# LIC_rack_ZM-01.net
KiCad netlist of a schematic drawn in EAGLE
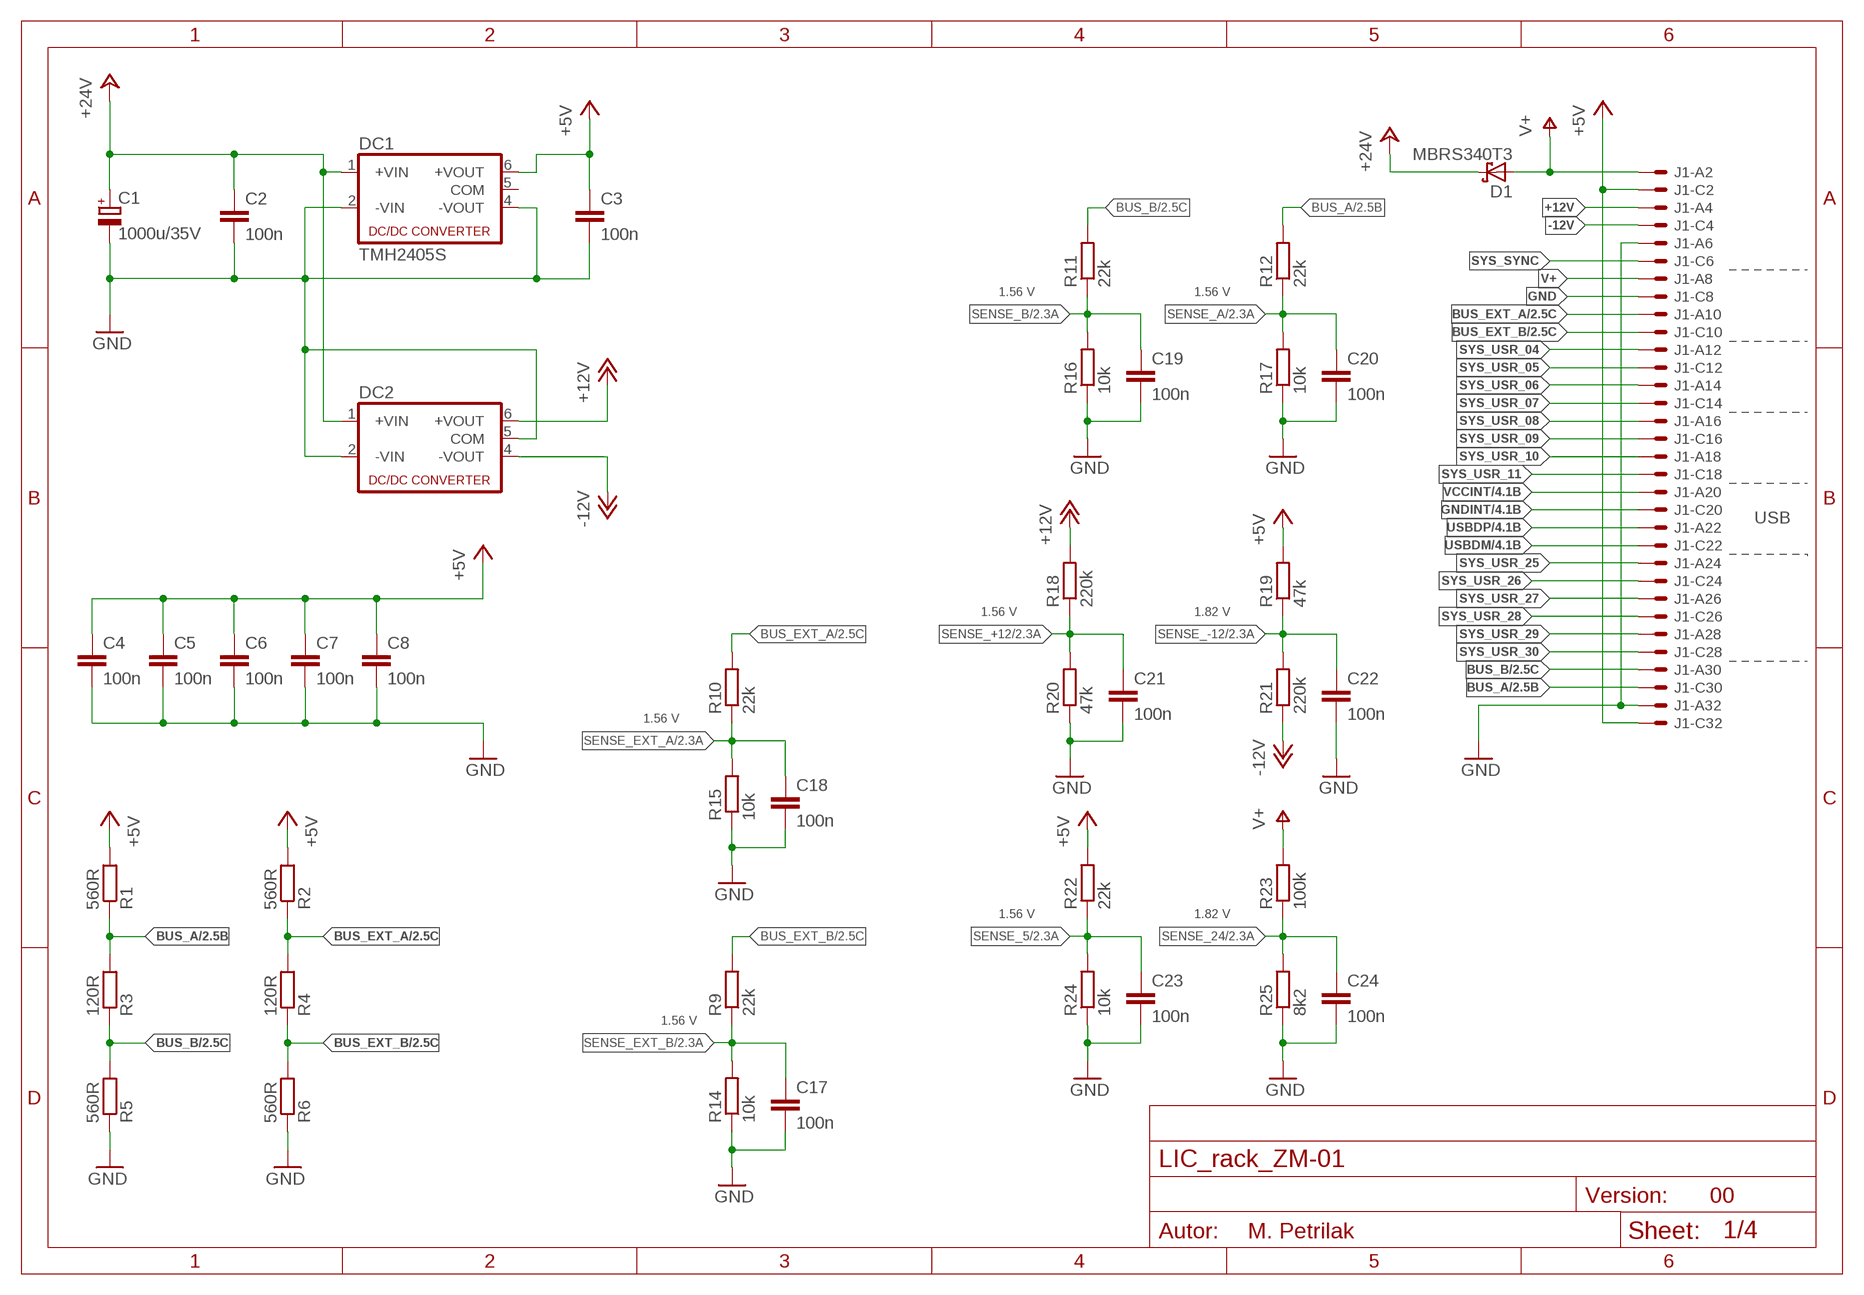
[diagram p0: schematic, sheet 1]
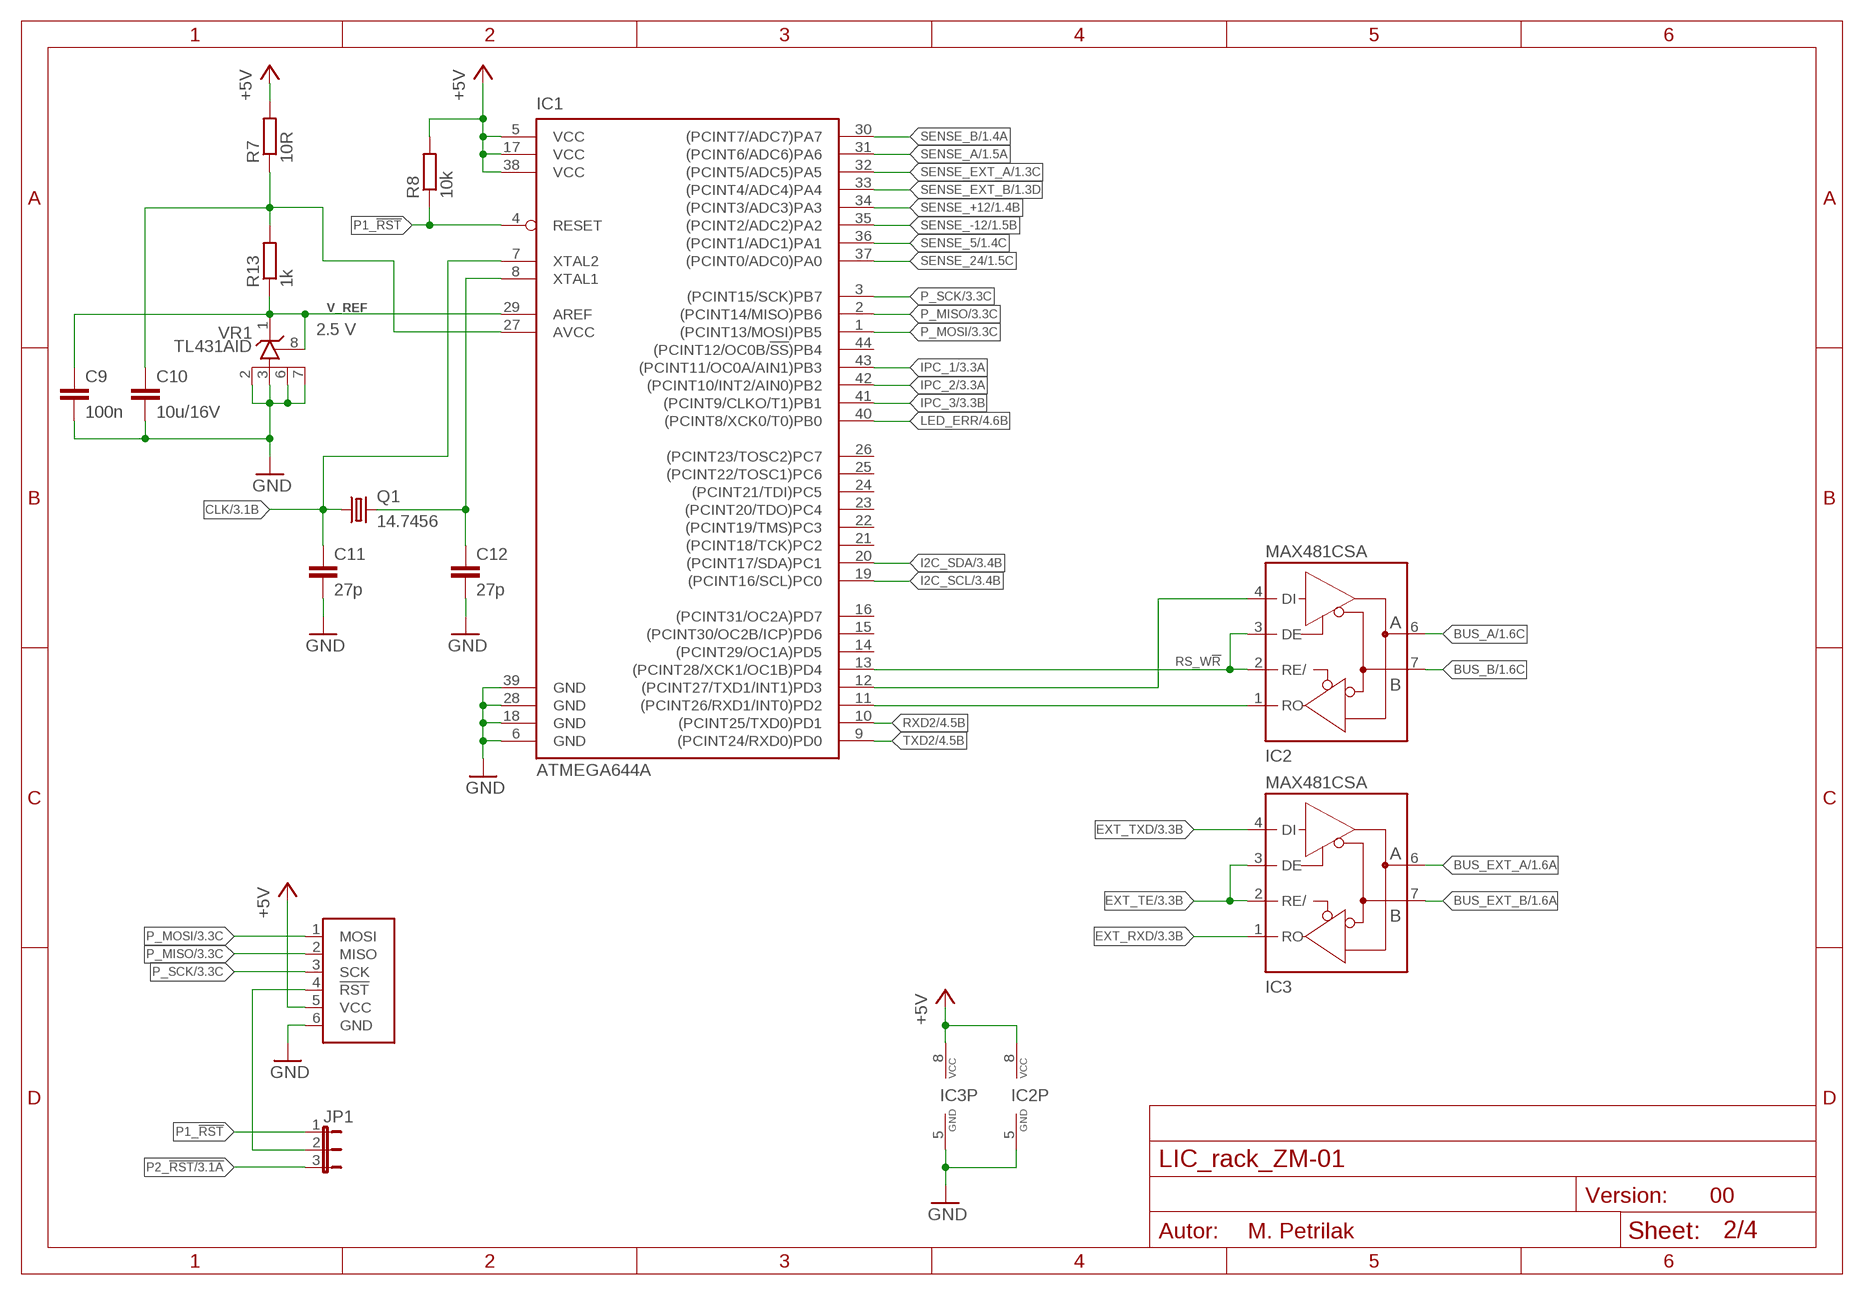
[diagram p1: schematic, sheet 2]
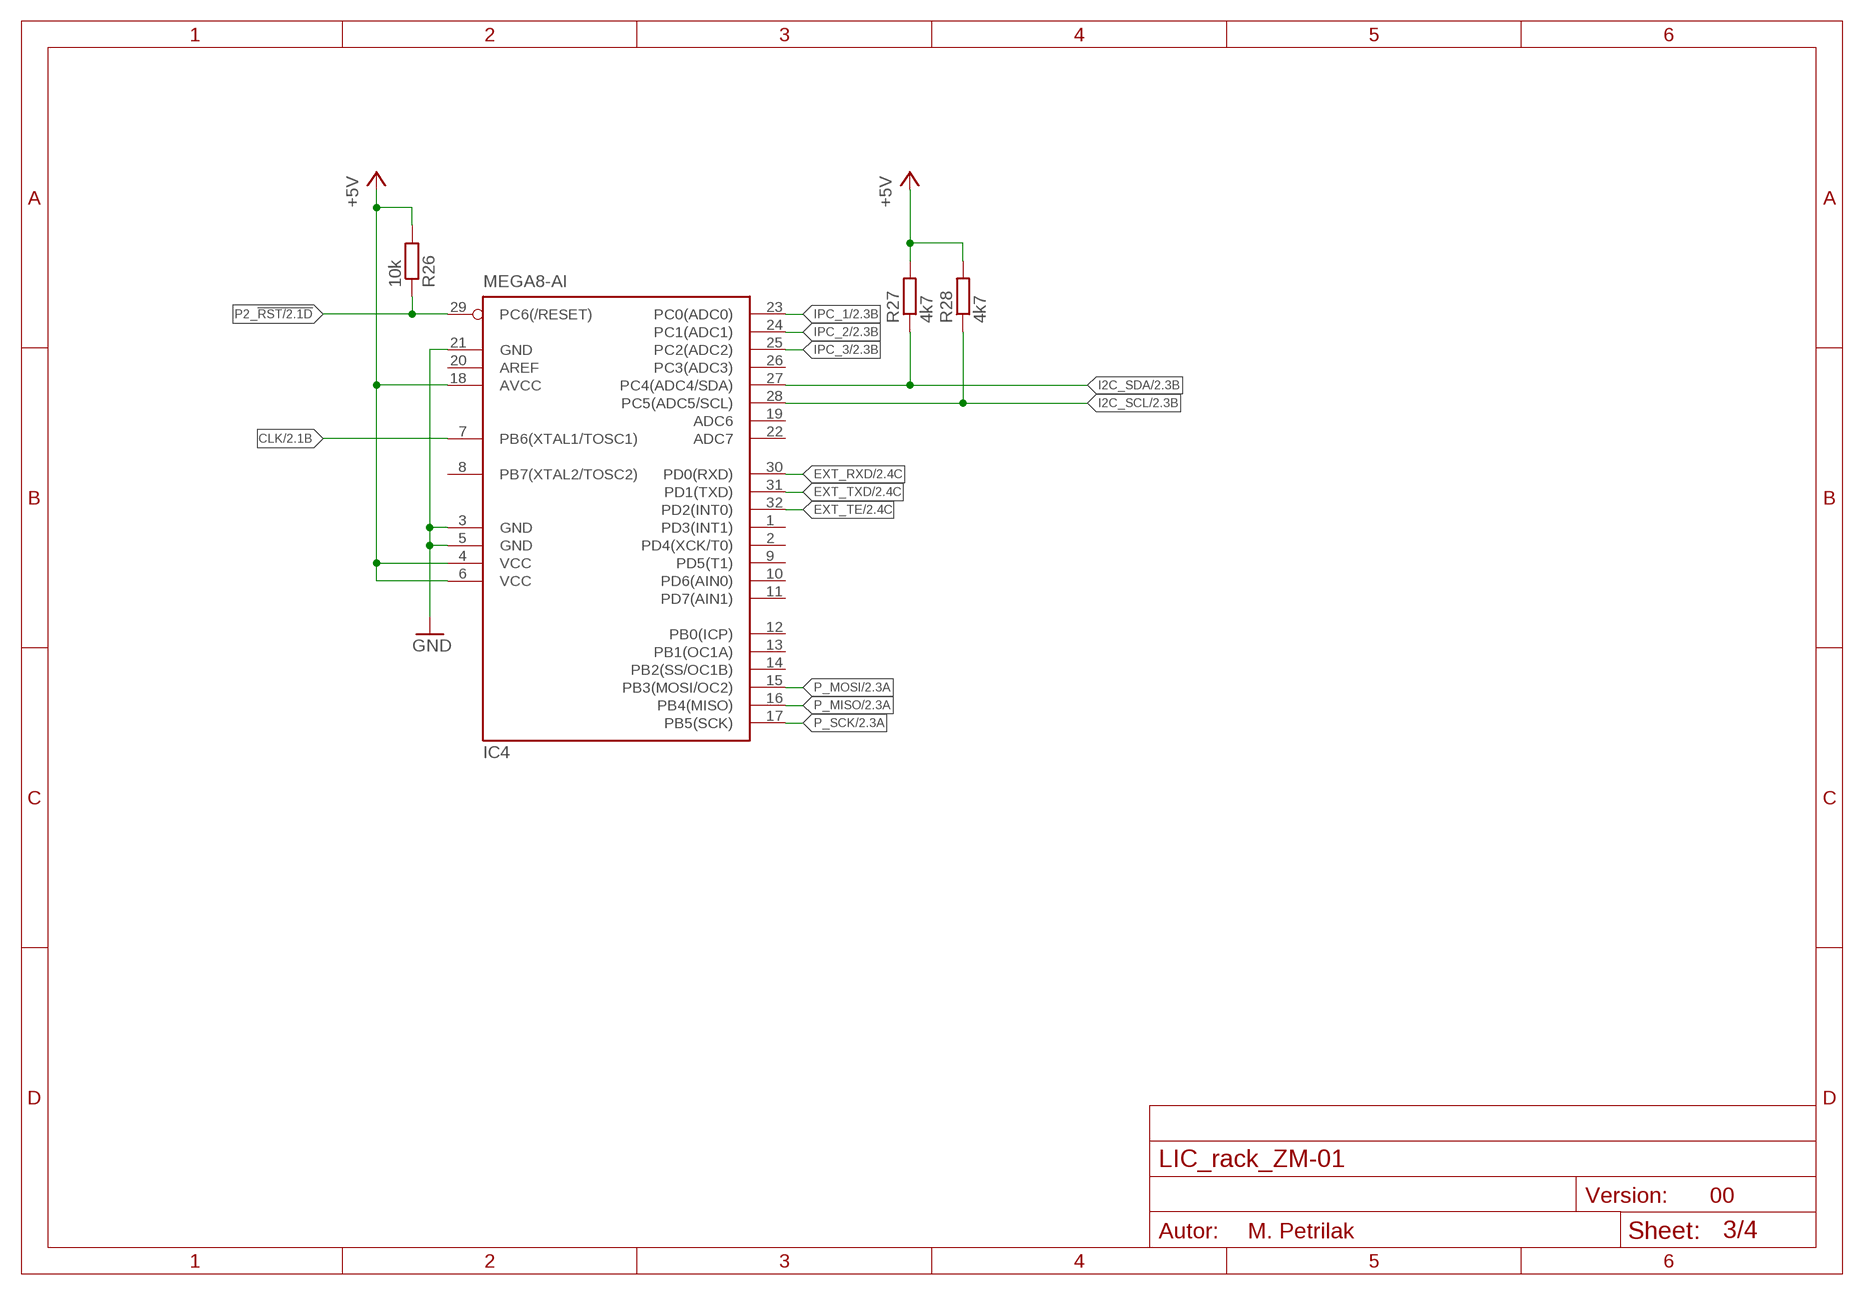
[diagram p2: schematic, sheet 3]
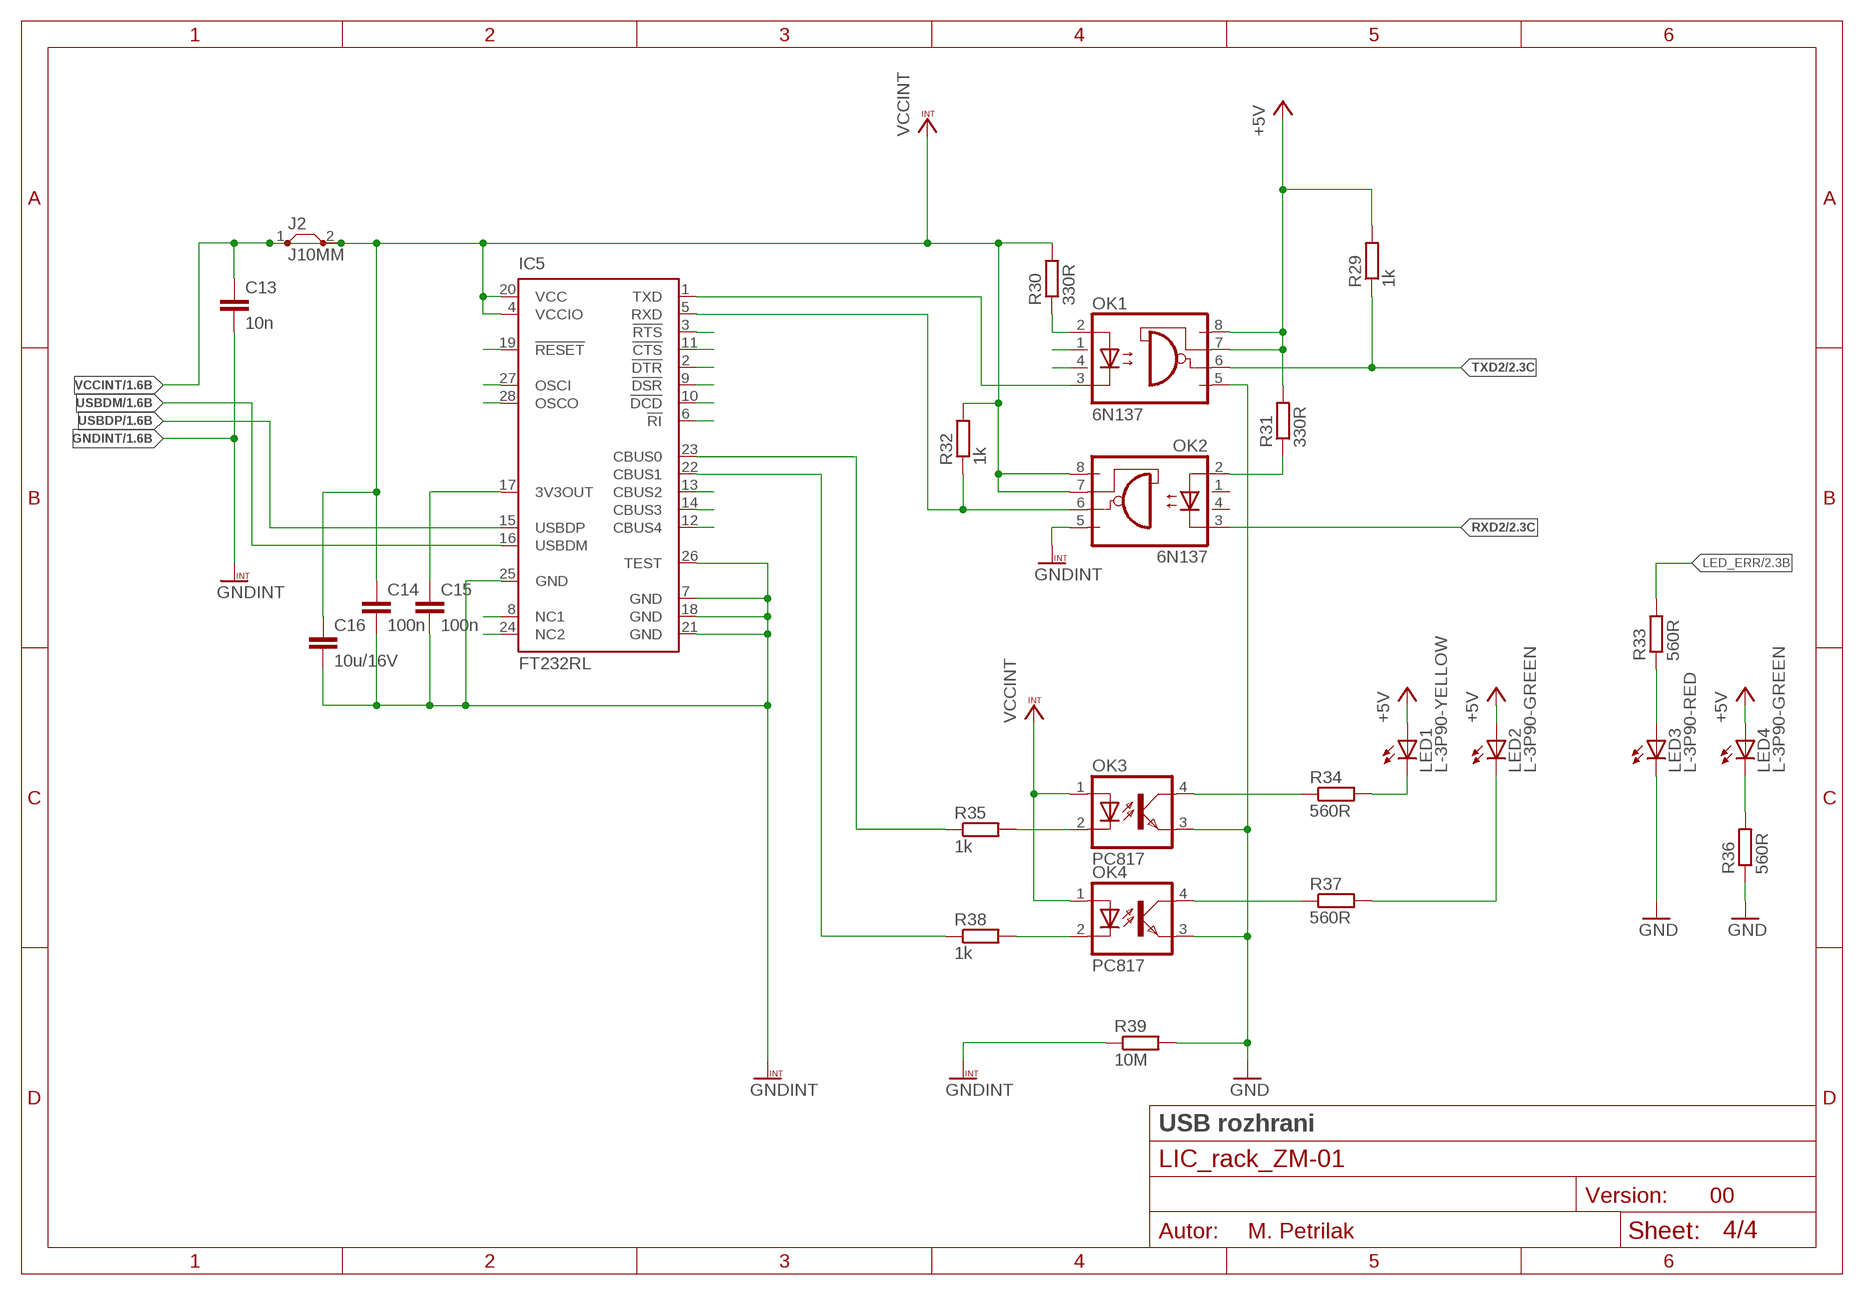
[diagram p3: schematic, sheet 4]

(export (version "E")
  (design (tool "Eeschema 10.0.6"))
  (components
    (comp (ref "C1")
      (value "1000u/35V")
      (footprint "eagle-import:E5-13X26-LR")
      (libsource (lib "eagle-import") (part "CPOL-EUE5-13X26-LR"))
    )
    (comp (ref "C2")
      (value "100n")
      (footprint "eagle-import:C1206")
      (libsource (lib "eagle-import") (part "C-EUC1206"))
    )
    (comp (ref "C3")
      (value "100n")
      (footprint "eagle-import:C1206")
      (libsource (lib "eagle-import") (part "C-EUC1206"))
    )
    (comp (ref "C4")
      (value "100n")
      (footprint "eagle-import:C1206")
      (libsource (lib "eagle-import") (part "C-EUC1206"))
    )
    (comp (ref "C5")
      (value "100n")
      (footprint "eagle-import:C1206")
      (libsource (lib "eagle-import") (part "C-EUC1206"))
    )
    (comp (ref "C6")
      (value "100n")
      (footprint "eagle-import:C1206")
      (libsource (lib "eagle-import") (part "C-EUC1206"))
    )
    (comp (ref "C7")
      (value "100n")
      (footprint "eagle-import:C1206")
      (libsource (lib "eagle-import") (part "C-EUC1206"))
    )
    (comp (ref "C8")
      (value "100n")
      (footprint "eagle-import:C1206")
      (libsource (lib "eagle-import") (part "C-EUC1206"))
    )
    (comp (ref "C17")
      (value "100n")
      (footprint "eagle-import:C1206")
      (libsource (lib "eagle-import") (part "C-EUC1206"))
    )
    (comp (ref "C18")
      (value "100n")
      (footprint "eagle-import:C1206")
      (libsource (lib "eagle-import") (part "C-EUC1206"))
    )
    (comp (ref "C19")
      (value "100n")
      (footprint "eagle-import:C1206")
      (libsource (lib "eagle-import") (part "C-EUC1206"))
    )
    (comp (ref "C20")
      (value "100n")
      (footprint "eagle-import:C1206")
      (libsource (lib "eagle-import") (part "C-EUC1206"))
    )
    (comp (ref "C21")
      (value "100n")
      (footprint "eagle-import:C1206")
      (libsource (lib "eagle-import") (part "C-EUC1206"))
    )
    (comp (ref "C22")
      (value "100n")
      (footprint "eagle-import:C1206")
      (libsource (lib "eagle-import") (part "C-EUC1206"))
    )
    (comp (ref "C23")
      (value "100n")
      (footprint "eagle-import:C1206")
      (libsource (lib "eagle-import") (part "C-EUC1206"))
    )
    (comp (ref "C24")
      (value "100n")
      (footprint "eagle-import:C1206")
      (libsource (lib "eagle-import") (part "C-EUC1206"))
    )
    (comp (ref "D1")
      (value "MBRS340T3")
      (footprint "eagle-import:SMC")
      (libsource (lib "eagle-import") (part "MBRS340T3"))
    )
    (comp (ref "DC1")
      (value "TMH2405S")
      (footprint "eagle-import:NMA")
      (libsource (lib "eagle-import") (part "NMA"))
    )
    (comp (ref "DC2")
      (value "NMA")
      (footprint "eagle-import:NMA")
      (libsource (lib "eagle-import") (part "NMA"))
    )
    (comp (ref "J1")
      (value "VG32SP")
      (footprint "eagle-import:VG32P")
      (libsource (lib "eagle-import") (part "VG32SP"))
    )
    (comp (ref "R1")
      (value "560R")
      (footprint "eagle-import:R1206")
      (libsource (lib "eagle-import") (part "R-EU_R1206"))
    )
    (comp (ref "R2")
      (value "560R")
      (footprint "eagle-import:R1206")
      (libsource (lib "eagle-import") (part "R-EU_R1206"))
    )
    (comp (ref "R3")
      (value "120R")
      (footprint "eagle-import:R1206")
      (libsource (lib "eagle-import") (part "R-EU_R1206"))
    )
    (comp (ref "R4")
      (value "120R")
      (footprint "eagle-import:R1206")
      (libsource (lib "eagle-import") (part "R-EU_R1206"))
    )
    (comp (ref "R5")
      (value "560R")
      (footprint "eagle-import:R1206")
      (libsource (lib "eagle-import") (part "R-EU_R1206"))
    )
    (comp (ref "R6")
      (value "560R")
      (footprint "eagle-import:R1206")
      (libsource (lib "eagle-import") (part "R-EU_R1206"))
    )
    (comp (ref "R9")
      (value "22k")
      (footprint "eagle-import:R1206")
      (libsource (lib "eagle-import") (part "R-EU_R1206"))
    )
    (comp (ref "R10")
      (value "22k")
      (footprint "eagle-import:R1206")
      (libsource (lib "eagle-import") (part "R-EU_R1206"))
    )
    (comp (ref "R11")
      (value "22k")
      (footprint "eagle-import:R1206")
      (libsource (lib "eagle-import") (part "R-EU_R1206"))
    )
    (comp (ref "R12")
      (value "22k")
      (footprint "eagle-import:R1206")
      (libsource (lib "eagle-import") (part "R-EU_R1206"))
    )
    (comp (ref "R14")
      (value "10k")
      (footprint "eagle-import:R1206")
      (libsource (lib "eagle-import") (part "R-EU_R1206"))
    )
    (comp (ref "R15")
      (value "10k")
      (footprint "eagle-import:R1206")
      (libsource (lib "eagle-import") (part "R-EU_R1206"))
    )
    (comp (ref "R16")
      (value "10k")
      (footprint "eagle-import:R1206")
      (libsource (lib "eagle-import") (part "R-EU_R1206"))
    )
    (comp (ref "R17")
      (value "10k")
      (footprint "eagle-import:R1206")
      (libsource (lib "eagle-import") (part "R-EU_R1206"))
    )
    (comp (ref "R18")
      (value "220k")
      (footprint "eagle-import:R1206")
      (libsource (lib "eagle-import") (part "R-EU_R1206"))
    )
    (comp (ref "R19")
      (value "47k")
      (footprint "eagle-import:R1206")
      (libsource (lib "eagle-import") (part "R-EU_R1206"))
    )
    (comp (ref "R20")
      (value "47k")
      (footprint "eagle-import:R1206")
      (libsource (lib "eagle-import") (part "R-EU_R1206"))
    )
    (comp (ref "R21")
      (value "220k")
      (footprint "eagle-import:R1206")
      (libsource (lib "eagle-import") (part "R-EU_R1206"))
    )
    (comp (ref "R22")
      (value "22k")
      (footprint "eagle-import:R1206")
      (libsource (lib "eagle-import") (part "R-EU_R1206"))
    )
    (comp (ref "R23")
      (value "100k")
      (footprint "eagle-import:R1206")
      (libsource (lib "eagle-import") (part "R-EU_R1206"))
    )
    (comp (ref "R24")
      (value "10k")
      (footprint "eagle-import:R1206")
      (libsource (lib "eagle-import") (part "R-EU_R1206"))
    )
    (comp (ref "R25")
      (value "8k2")
      (footprint "eagle-import:R1206")
      (libsource (lib "eagle-import") (part "R-EU_R1206"))
    )
    (comp (ref "C9")
      (value "100n")
      (footprint "eagle-import:C1206")
      (libsource (lib "eagle-import") (part "C-EUC1206"))
    )
    (comp (ref "C10")
      (value "10u/16V")
      (footprint "eagle-import:C1206")
      (libsource (lib "eagle-import") (part "C-EUC1206"))
    )
    (comp (ref "C11")
      (value "27p")
      (footprint "eagle-import:C0805")
      (libsource (lib "eagle-import") (part "C-EUC0805"))
    )
    (comp (ref "C12")
      (value "27p")
      (footprint "eagle-import:C0805")
      (libsource (lib "eagle-import") (part "C-EUC0805"))
    )
    (comp (ref "IC1")
      (value "ATMEGA644A")
      (footprint "eagle-import:TQFP44")
      (libsource (lib "eagle-import") (part "ATMEGA644A"))
    )
    (comp (ref "IC2")
      (value "MAX481CSA")
      (footprint "eagle-import:SO08")
      (libsource (lib "eagle-import") (part "MAX481CSA"))
    )
    (comp (ref "IC3")
      (value "MAX481CSA")
      (footprint "eagle-import:SO08")
      (libsource (lib "eagle-import") (part "MAX481CSA"))
    )
    (comp (ref "JP1")
      (value "JP2E")
      (footprint "eagle-import:JP2")
      (libsource (lib "eagle-import") (part "JP2E"))
    )
    (comp (ref "Q1")
      (value "14.7456")
      (footprint "eagle-import:HC49U70")
      (libsource (lib "eagle-import") (part "XTAL"))
    )
    (comp (ref "R7")
      (value "10R")
      (footprint "eagle-import:R1206")
      (libsource (lib "eagle-import") (part "R-EU_R1206"))
    )
    (comp (ref "R8")
      (value "10k")
      (footprint "eagle-import:R1206")
      (libsource (lib "eagle-import") (part "R-EU_R1206"))
    )
    (comp (ref "R13")
      (value "1k")
      (footprint "eagle-import:R1206")
      (libsource (lib "eagle-import") (part "R-EU_R1206"))
    )
    (comp (ref "U1")
      (value "ATPROG-V")
      (footprint "eagle-import:6410-06")
      (libsource (lib "eagle-import") (part "ATPROG-V"))
    )
    (comp (ref "VR1")
      (value "TL431AID")
      (footprint "eagle-import:SO-08")
      (libsource (lib "eagle-import") (part "TL431-SMD"))
    )
    (comp (ref "IC4")
      (value "MEGA8-AI")
      (footprint "eagle-import:TQFP32-08")
      (libsource (lib "eagle-import") (part "MEGA8-AI"))
    )
    (comp (ref "R26")
      (value "10k")
      (footprint "eagle-import:R1206")
      (libsource (lib "eagle-import") (part "R-EU_R1206"))
    )
    (comp (ref "R27")
      (value "4k7")
      (footprint "eagle-import:R1206")
      (libsource (lib "eagle-import") (part "R-EU_R1206"))
    )
    (comp (ref "R28")
      (value "4k7")
      (footprint "eagle-import:R1206")
      (libsource (lib "eagle-import") (part "R-EU_R1206"))
    )
    (comp (ref "C13")
      (value "10n")
      (footprint "eagle-import:C0805")
      (libsource (lib "eagle-import") (part "C-EUC0805"))
    )
    (comp (ref "C14")
      (value "100n")
      (footprint "eagle-import:C1206")
      (libsource (lib "eagle-import") (part "C-EUC1206"))
    )
    (comp (ref "C15")
      (value "100n")
      (footprint "eagle-import:C1206")
      (libsource (lib "eagle-import") (part "C-EUC1206"))
    )
    (comp (ref "C16")
      (value "10u/16V")
      (footprint "eagle-import:C1206")
      (libsource (lib "eagle-import") (part "C-EUC1206"))
    )
    (comp (ref "IC5")
      (value "FT232RL")
      (footprint "eagle-import:SSOP28")
      (libsource (lib "eagle-import") (part "FT232RL"))
    )
    (comp (ref "J2")
      (value "J10MM")
      (footprint "eagle-import:10")
      (libsource (lib "eagle-import") (part "J10MM"))
    )
    (comp (ref "LED1")
      (value "L-3P90-YELLOW")
      (footprint "eagle-import:L-3P90")
      (libsource (lib "eagle-import") (part "L-3P90-YELLOW"))
    )
    (comp (ref "LED2")
      (value "L-3P90-GREEN")
      (footprint "eagle-import:L-3P90")
      (libsource (lib "eagle-import") (part "L-3P90-GREEN"))
    )
    (comp (ref "LED3")
      (value "L-3P90-RED")
      (footprint "eagle-import:L-3P90")
      (libsource (lib "eagle-import") (part "L-3P90-RED"))
    )
    (comp (ref "LED4")
      (value "L-3P90-GREEN")
      (footprint "eagle-import:L-3P90")
      (libsource (lib "eagle-import") (part "L-3P90-GREEN"))
    )
    (comp (ref "OK1")
      (value "6N137")
      (footprint "eagle-import:DIL08")
      (libsource (lib "eagle-import") (part "6N137"))
    )
    (comp (ref "OK2")
      (value "6N137")
      (footprint "eagle-import:DIL08")
      (libsource (lib "eagle-import") (part "6N137"))
    )
    (comp (ref "OK3")
      (value "PC817")
      (footprint "eagle-import:DIL04")
      (libsource (lib "eagle-import") (part "PC817"))
    )
    (comp (ref "OK4")
      (value "PC817")
      (footprint "eagle-import:DIL04")
      (libsource (lib "eagle-import") (part "PC817"))
    )
    (comp (ref "R29")
      (value "1k")
      (footprint "eagle-import:R1206")
      (libsource (lib "eagle-import") (part "R-EU_R1206"))
    )
    (comp (ref "R30")
      (value "330R")
      (footprint "eagle-import:R1206")
      (libsource (lib "eagle-import") (part "R-EU_R1206"))
    )
    (comp (ref "R31")
      (value "330R")
      (footprint "eagle-import:R1206")
      (libsource (lib "eagle-import") (part "R-EU_R1206"))
    )
    (comp (ref "R32")
      (value "1k")
      (footprint "eagle-import:R1206")
      (libsource (lib "eagle-import") (part "R-EU_R1206"))
    )
    (comp (ref "R33")
      (value "560R")
      (footprint "eagle-import:R1206")
      (libsource (lib "eagle-import") (part "R-EU_R1206"))
    )
    (comp (ref "R34")
      (value "560R")
      (footprint "eagle-import:R1206")
      (libsource (lib "eagle-import") (part "R-EU_R1206"))
    )
    (comp (ref "R35")
      (value "1k")
      (footprint "eagle-import:R1206")
      (libsource (lib "eagle-import") (part "R-EU_R1206"))
    )
    (comp (ref "R36")
      (value "560R")
      (footprint "eagle-import:R1206")
      (libsource (lib "eagle-import") (part "R-EU_R1206"))
    )
    (comp (ref "R37")
      (value "560R")
      (footprint "eagle-import:R1206")
      (libsource (lib "eagle-import") (part "R-EU_R1206"))
    )
    (comp (ref "R38")
      (value "1k")
      (footprint "eagle-import:R1206")
      (libsource (lib "eagle-import") (part "R-EU_R1206"))
    )
    (comp (ref "R39")
      (value "10M")
      (footprint "eagle-import:R1206")
      (libsource (lib "eagle-import") (part "R-EU_R1206"))
    )
  )
  (nets
    (net (code "1") (name "+5V") (class "Default")
      (node (ref "C3") (pin "1") (pinfunction "1_1") (pintype "passive"))
      (node (ref "C4") (pin "1") (pinfunction "1_1") (pintype "passive"))
      (node (ref "C5") (pin "1") (pinfunction "1_1") (pintype "passive"))
      (node (ref "C6") (pin "1") (pinfunction "1_1") (pintype "passive"))
      (node (ref "C7") (pin "1") (pinfunction "1_1") (pintype "passive"))
      (node (ref "C8") (pin "1") (pinfunction "1_1") (pintype "passive"))
      (node (ref "DC1") (pin "6") (pinfunction "+VOUT_6") (pintype "passive"))
      (node (ref "IC1") (pin "17") (pinfunction "VCC_17") (pintype "power_in"))
      (node (ref "IC1") (pin "38") (pinfunction "VCC_38") (pintype "power_in"))
      (node (ref "IC1") (pin "5") (pinfunction "VCC_5") (pintype "power_in"))
      (node (ref "IC2") (pin "8") (pinfunction "VCC_8") (pintype "power_in"))
      (node (ref "IC3") (pin "8") (pinfunction "VCC_8") (pintype "power_in"))
      (node (ref "IC4") (pin "18") (pinfunction "AVCC_18") (pintype "power_in"))
      (node (ref "IC4") (pin "4") (pinfunction "VCC_4") (pintype "power_in"))
      (node (ref "IC4") (pin "6") (pinfunction "VCC_6") (pintype "power_in"))
      (node (ref "J1") (pin "C2") (pinfunction "MS_C2") (pintype "passive"))
      (node (ref "J1") (pin "C32") (pinfunction "MSV_C32") (pintype "passive"))
      (node (ref "LED1") (pin "A") (pinfunction "A_A") (pintype "passive"))
      (node (ref "LED2") (pin "A") (pinfunction "A_A") (pintype "passive"))
      (node (ref "LED4") (pin "A") (pinfunction "A_A") (pintype "passive"))
      (node (ref "OK1") (pin "7") (pinfunction "VE_7") (pintype "passive"))
      (node (ref "OK1") (pin "8") (pinfunction "VCC_8") (pintype "passive"))
      (node (ref "R1") (pin "2") (pinfunction "2_2") (pintype "passive"))
      (node (ref "R19") (pin "2") (pinfunction "2_2") (pintype "passive"))
      (node (ref "R2") (pin "2") (pinfunction "2_2") (pintype "passive"))
      (node (ref "R22") (pin "2") (pinfunction "2_2") (pintype "passive"))
      (node (ref "R26") (pin "2") (pinfunction "2_2") (pintype "passive"))
      (node (ref "R27") (pin "2") (pinfunction "2_2") (pintype "passive"))
      (node (ref "R28") (pin "2") (pinfunction "2_2") (pintype "passive"))
      (node (ref "R29") (pin "2") (pinfunction "2_2") (pintype "passive"))
      (node (ref "R31") (pin "2") (pinfunction "2_2") (pintype "passive"))
      (node (ref "R7") (pin "2") (pinfunction "2_2") (pintype "passive"))
      (node (ref "R8") (pin "2") (pinfunction "2_2") (pintype "passive"))
      (node (ref "U1") (pin "5") (pinfunction "VCC_5") (pintype "power_in"))
    )
    (net (code "2") (name "+12V") (class "Default")
      (node (ref "DC2") (pin "6") (pinfunction "+VOUT_6") (pintype "passive"))
      (node (ref "J1") (pin "A4") (pinfunction "MS_A4") (pintype "passive"))
      (node (ref "R18") (pin "2") (pinfunction "2_2") (pintype "passive"))
    )
    (net (code "3") (name "+24V") (class "Default")
      (node (ref "C1") (pin "+") (pinfunction "+_+") (pintype "passive"))
      (node (ref "C2") (pin "1") (pinfunction "1_1") (pintype "passive"))
      (node (ref "D1") (pin "C") (pinfunction "C_C") (pintype "passive"))
      (node (ref "DC1") (pin "1") (pinfunction "+VIN_1") (pintype "passive"))
      (node (ref "DC2") (pin "1") (pinfunction "+VIN_1") (pintype "passive"))
    )
    (net (code "4") (name "-12V") (class "Default")
      (node (ref "DC2") (pin "4") (pinfunction "-VOUT_4") (pintype "passive"))
      (node (ref "J1") (pin "C4") (pinfunction "MS_C4") (pintype "passive"))
      (node (ref "R21") (pin "1") (pinfunction "1_1") (pintype "passive"))
    )
    (net (code "5") (name "BUS_A") (class "Default")
      (node (ref "IC2") (pin "6") (pinfunction "A_6") (pintype "passive"))
      (node (ref "J1") (pin "C30") (pinfunction "MS_C30") (pintype "passive"))
      (node (ref "R1") (pin "1") (pinfunction "1_1") (pintype "passive"))
      (node (ref "R12") (pin "2") (pinfunction "2_2") (pintype "passive"))
      (node (ref "R3") (pin "2") (pinfunction "2_2") (pintype "passive"))
    )
    (net (code "6") (name "BUS_B") (class "Default")
      (node (ref "IC2") (pin "7") (pinfunction "B_7") (pintype "passive"))
      (node (ref "J1") (pin "A30") (pinfunction "MS_A30") (pintype "passive"))
      (node (ref "R11") (pin "2") (pinfunction "2_2") (pintype "passive"))
      (node (ref "R3") (pin "1") (pinfunction "1_1") (pintype "passive"))
      (node (ref "R5") (pin "2") (pinfunction "2_2") (pintype "passive"))
    )
    (net (code "7") (name "BUS_EXT_A") (class "Default")
      (node (ref "IC3") (pin "6") (pinfunction "A_6") (pintype "passive"))
      (node (ref "J1") (pin "A10") (pinfunction "MS_A10") (pintype "passive"))
      (node (ref "R10") (pin "2") (pinfunction "2_2") (pintype "passive"))
      (node (ref "R2") (pin "1") (pinfunction "1_1") (pintype "passive"))
      (node (ref "R4") (pin "2") (pinfunction "2_2") (pintype "passive"))
    )
    (net (code "8") (name "BUS_EXT_B") (class "Default")
      (node (ref "IC3") (pin "7") (pinfunction "B_7") (pintype "passive"))
      (node (ref "J1") (pin "C10") (pinfunction "MS_C10") (pintype "passive"))
      (node (ref "R4") (pin "1") (pinfunction "1_1") (pintype "passive"))
      (node (ref "R6") (pin "2") (pinfunction "2_2") (pintype "passive"))
      (node (ref "R9") (pin "2") (pinfunction "2_2") (pintype "passive"))
    )
    (net (code "9") (name "CLK") (class "Default")
      (node (ref "C11") (pin "1") (pinfunction "1_1") (pintype "passive"))
      (node (ref "IC1") (pin "7") (pinfunction "XTAL2_7") (pintype "bidirectional"))
      (node (ref "IC4") (pin "7") (pinfunction "PB6(XTAL1/TOSC1)_7") (pintype "bidirectional"))
      (node (ref "Q1") (pin "1") (pinfunction "1_1") (pintype "passive"))
    )
    (net (code "10") (name "EXT_RXD") (class "Default")
      (node (ref "IC3") (pin "1") (pinfunction "RO_1") (pintype "output"))
      (node (ref "IC4") (pin "30") (pinfunction "PD0(RXD)_30") (pintype "bidirectional"))
    )
    (net (code "11") (name "EXT_TE") (class "Default")
      (node (ref "IC3") (pin "2") (pinfunction "RE/_2") (pintype "input"))
      (node (ref "IC3") (pin "3") (pinfunction "DE_3") (pintype "input"))
      (node (ref "IC4") (pin "32") (pinfunction "PD2(INT0)_32") (pintype "bidirectional"))
    )
    (net (code "12") (name "EXT_TXD") (class "Default")
      (node (ref "IC3") (pin "4") (pinfunction "DI_4") (pintype "input"))
      (node (ref "IC4") (pin "31") (pinfunction "PD1(TXD)_31") (pintype "bidirectional"))
    )
    (net (code "13") (name "GND") (class "Default")
      (node (ref "C1") (pin "-") (pinfunction "-_-") (pintype "passive"))
      (node (ref "C10") (pin "2") (pinfunction "2_2") (pintype "passive"))
      (node (ref "C11") (pin "2") (pinfunction "2_2") (pintype "passive"))
      (node (ref "C12") (pin "2") (pinfunction "2_2") (pintype "passive"))
      (node (ref "C17") (pin "2") (pinfunction "2_2") (pintype "passive"))
      (node (ref "C18") (pin "2") (pinfunction "2_2") (pintype "passive"))
      (node (ref "C19") (pin "2") (pinfunction "2_2") (pintype "passive"))
      (node (ref "C2") (pin "2") (pinfunction "2_2") (pintype "passive"))
      (node (ref "C20") (pin "2") (pinfunction "2_2") (pintype "passive"))
      (node (ref "C21") (pin "2") (pinfunction "2_2") (pintype "passive"))
      (node (ref "C22") (pin "2") (pinfunction "2_2") (pintype "passive"))
      (node (ref "C23") (pin "2") (pinfunction "2_2") (pintype "passive"))
      (node (ref "C24") (pin "2") (pinfunction "2_2") (pintype "passive"))
      (node (ref "C3") (pin "2") (pinfunction "2_2") (pintype "passive"))
      (node (ref "C4") (pin "2") (pinfunction "2_2") (pintype "passive"))
      (node (ref "C5") (pin "2") (pinfunction "2_2") (pintype "passive"))
      (node (ref "C6") (pin "2") (pinfunction "2_2") (pintype "passive"))
      (node (ref "C7") (pin "2") (pinfunction "2_2") (pintype "passive"))
      (node (ref "C8") (pin "2") (pinfunction "2_2") (pintype "passive"))
      (node (ref "C9") (pin "2") (pinfunction "2_2") (pintype "passive"))
      (node (ref "DC1") (pin "2") (pinfunction "-VIN_2") (pintype "passive"))
      (node (ref "DC1") (pin "4") (pinfunction "-VOUT_4") (pintype "passive"))
      (node (ref "DC2") (pin "2") (pinfunction "-VIN_2") (pintype "passive"))
      (node (ref "DC2") (pin "5") (pinfunction "COM_5") (pintype "passive"))
      (node (ref "IC1") (pin "18") (pinfunction "GND_18") (pintype "power_in"))
      (node (ref "IC1") (pin "28") (pinfunction "GND_28") (pintype "power_in"))
      (node (ref "IC1") (pin "39") (pinfunction "GND_39") (pintype "power_in"))
      (node (ref "IC1") (pin "6") (pinfunction "GND_6") (pintype "power_in"))
      (node (ref "IC2") (pin "5") (pinfunction "GND_5") (pintype "power_in"))
      (node (ref "IC3") (pin "5") (pinfunction "GND_5") (pintype "power_in"))
      (node (ref "IC4") (pin "21") (pinfunction "GND_21") (pintype "power_in"))
      (node (ref "IC4") (pin "3") (pinfunction "GND_3") (pintype "power_in"))
      (node (ref "IC4") (pin "5") (pinfunction "GND_5") (pintype "power_in"))
      (node (ref "J1") (pin "A32") (pinfunction "MS_A32") (pintype "passive"))
      (node (ref "J1") (pin "A6") (pinfunction "MS_A6") (pintype "passive"))
      (node (ref "J1") (pin "C8") (pinfunction "MS_C8") (pintype "passive"))
      (node (ref "LED3") (pin "K") (pinfunction "C_K") (pintype "passive"))
      (node (ref "OK1") (pin "5") (pinfunction "GND_5") (pintype "passive"))
      (node (ref "OK3") (pin "3") (pinfunction "EMIT_3") (pintype "passive"))
      (node (ref "OK4") (pin "3") (pinfunction "EMIT_3") (pintype "passive"))
      (node (ref "R14") (pin "1") (pinfunction "1_1") (pintype "passive"))
      (node (ref "R15") (pin "1") (pinfunction "1_1") (pintype "passive"))
      (node (ref "R16") (pin "1") (pinfunction "1_1") (pintype "passive"))
      (node (ref "R17") (pin "1") (pinfunction "1_1") (pintype "passive"))
      (node (ref "R20") (pin "1") (pinfunction "1_1") (pintype "passive"))
      (node (ref "R24") (pin "1") (pinfunction "1_1") (pintype "passive"))
      (node (ref "R25") (pin "1") (pinfunction "1_1") (pintype "passive"))
      (node (ref "R36") (pin "1") (pinfunction "1_1") (pintype "passive"))
      (node (ref "R39") (pin "2") (pinfunction "2_2") (pintype "passive"))
      (node (ref "R5") (pin "1") (pinfunction "1_1") (pintype "passive"))
      (node (ref "R6") (pin "1") (pinfunction "1_1") (pintype "passive"))
      (node (ref "U1") (pin "6") (pinfunction "GND_6") (pintype "power_in"))
      (node (ref "VR1") (pin "2") (pinfunction "A3_2") (pintype "passive"))
      (node (ref "VR1") (pin "3") (pinfunction "A2_3") (pintype "passive"))
      (node (ref "VR1") (pin "6") (pinfunction "A1_6") (pintype "passive"))
      (node (ref "VR1") (pin "7") (pinfunction "A_7") (pintype "passive"))
    )
    (net (code "14") (name "GNDINT") (class "Default")
      (node (ref "C13") (pin "2") (pinfunction "2_2") (pintype "passive"))
      (node (ref "C14") (pin "2") (pinfunction "2_2") (pintype "passive"))
      (node (ref "C15") (pin "2") (pinfunction "2_2") (pintype "passive"))
      (node (ref "C16") (pin "2") (pinfunction "2_2") (pintype "passive"))
      (node (ref "IC5") (pin "18") (pinfunction "GND_18") (pintype "power_in"))
      (node (ref "IC5") (pin "21") (pinfunction "GND_21") (pintype "power_in"))
      (node (ref "IC5") (pin "25") (pinfunction "GND_25") (pintype "power_in"))
      (node (ref "IC5") (pin "26") (pinfunction "TEST_26") (pintype "input"))
      (node (ref "IC5") (pin "7") (pinfunction "GND_7") (pintype "power_in"))
      (node (ref "J1") (pin "C20") (pinfunction "MS_C20") (pintype "passive"))
      (node (ref "OK2") (pin "5") (pinfunction "GND_5") (pintype "passive"))
      (node (ref "R39") (pin "1") (pinfunction "1_1") (pintype "passive"))
    )
    (net (code "15") (name "I2C_SCL") (class "Default")
      (node (ref "IC1") (pin "19") (pinfunction "(PCINT16/SCL)PC0_19") (pintype "output"))
      (node (ref "IC4") (pin "28") (pinfunction "PC5(ADC5/SCL)_28") (pintype "bidirectional"))
      (node (ref "R28") (pin "1") (pinfunction "1_1") (pintype "passive"))
    )
    (net (code "16") (name "I2C_SDA") (class "Default")
      (node (ref "IC1") (pin "20") (pinfunction "(PCINT17/SDA)PC1_20") (pintype "output"))
      (node (ref "IC4") (pin "27") (pinfunction "PC4(ADC4/SDA)_27") (pintype "bidirectional"))
      (node (ref "R27") (pin "1") (pinfunction "1_1") (pintype "passive"))
    )
    (net (code "17") (name "IPC_1") (class "Default")
      (node (ref "IC1") (pin "43") (pinfunction "(PCINT11/OC0A/AIN1)PB3_43") (pintype "bidirectional"))
      (node (ref "IC4") (pin "23") (pinfunction "PC0(ADC0)_23") (pintype "bidirectional"))
    )
    (net (code "18") (name "IPC_2") (class "Default")
      (node (ref "IC1") (pin "42") (pinfunction "(PCINT10/INT2/AIN0)PB2_42") (pintype "bidirectional"))
      (node (ref "IC4") (pin "24") (pinfunction "PC1(ADC1)_24") (pintype "bidirectional"))
    )
    (net (code "19") (name "IPC_3") (class "Default")
      (node (ref "IC1") (pin "41") (pinfunction "(PCINT9/CLKO/T1)PB1_41") (pintype "bidirectional"))
      (node (ref "IC4") (pin "25") (pinfunction "PC2(ADC2)_25") (pintype "bidirectional"))
    )
    (net (code "20") (name "LED_ERR") (class "Default")
      (node (ref "IC1") (pin "40") (pinfunction "(PCINT8/XCK0/T0)PB0_40") (pintype "bidirectional"))
      (node (ref "R33") (pin "2") (pinfunction "2_2") (pintype "passive"))
    )
    (net (code "21") (name "Net-(IC1-(PCINT26{slash}RXD1{slash}INT0)PD2)") (class "Default")
      (node (ref "IC1") (pin "11") (pinfunction "(PCINT26/RXD1/INT0)PD2_11") (pintype "bidirectional"))
      (node (ref "IC2") (pin "1") (pinfunction "RO_1") (pintype "output"))
    )
    (net (code "22") (name "Net-(IC1-(PCINT27{slash}TXD1{slash}INT1)PD3)") (class "Default")
      (node (ref "IC1") (pin "12") (pinfunction "(PCINT27/TXD1/INT1)PD3_12") (pintype "bidirectional"))
      (node (ref "IC2") (pin "4") (pinfunction "DI_4") (pintype "input"))
    )
    (net (code "23") (name "Net-(IC1-AVCC)") (class "Default")
      (node (ref "C10") (pin "1") (pinfunction "1_1") (pintype "passive"))
      (node (ref "IC1") (pin "27") (pinfunction "AVCC_27") (pintype "power_in"))
      (node (ref "R13") (pin "2") (pinfunction "2_2") (pintype "passive"))
      (node (ref "R7") (pin "1") (pinfunction "1_1") (pintype "passive"))
    )
    (net (code "24") (name "Net-(IC1-XTAL1)") (class "Default")
      (node (ref "C12") (pin "1") (pinfunction "1_1") (pintype "passive"))
      (node (ref "IC1") (pin "8") (pinfunction "XTAL1_8") (pintype "bidirectional"))
      (node (ref "Q1") (pin "2") (pinfunction "2_2") (pintype "passive"))
    )
    (net (code "25") (name "Net-(IC5-3V3OUT)") (class "Default")
      (node (ref "C15") (pin "1") (pinfunction "1_1") (pintype "passive"))
      (node (ref "IC5") (pin "17") (pinfunction "3V3OUT_17") (pintype "output"))
    )
    (net (code "26") (name "Net-(IC5-CBUS0)") (class "Default")
      (node (ref "IC5") (pin "23") (pinfunction "CBUS0_23") (pintype "bidirectional"))
      (node (ref "R35") (pin "1") (pinfunction "1_1") (pintype "passive"))
    )
    (net (code "27") (name "Net-(IC5-CBUS1)") (class "Default")
      (node (ref "IC5") (pin "22") (pinfunction "CBUS1_22") (pintype "bidirectional"))
      (node (ref "R38") (pin "1") (pinfunction "1_1") (pintype "passive"))
    )
    (net (code "28") (name "Net-(IC5-RXD)") (class "Default")
      (node (ref "IC5") (pin "5") (pinfunction "RXD_5") (pintype "input"))
      (node (ref "OK2") (pin "6") (pinfunction "VO_6") (pintype "passive"))
      (node (ref "R32") (pin "1") (pinfunction "1_1") (pintype "passive"))
    )
    (net (code "29") (name "Net-(IC5-TXD)") (class "Default")
      (node (ref "IC5") (pin "1") (pinfunction "TXD_1") (pintype "output"))
      (node (ref "OK1") (pin "3") (pinfunction "C_3") (pintype "passive"))
    )
    (net (code "30") (name "Net-(LED1-C)") (class "Default")
      (node (ref "LED1") (pin "K") (pinfunction "C_K") (pintype "passive"))
      (node (ref "R34") (pin "2") (pinfunction "2_2") (pintype "passive"))
    )
    (net (code "31") (name "Net-(LED2-C)") (class "Default")
      (node (ref "LED2") (pin "K") (pinfunction "C_K") (pintype "passive"))
      (node (ref "R37") (pin "2") (pinfunction "2_2") (pintype "passive"))
    )
    (net (code "32") (name "Net-(LED3-PadA)") (class "Default")
      (node (ref "LED3") (pin "A") (pinfunction "A_A") (pintype "passive"))
      (node (ref "R33") (pin "1") (pinfunction "1_1") (pintype "passive"))
    )
    (net (code "33") (name "Net-(LED4-C)") (class "Default")
      (node (ref "LED4") (pin "K") (pinfunction "C_K") (pintype "passive"))
      (node (ref "R36") (pin "2") (pinfunction "2_2") (pintype "passive"))
    )
    (net (code "34") (name "Net-(OK1-A)") (class "Default")
      (node (ref "OK1") (pin "2") (pinfunction "A_2") (pintype "passive"))
      (node (ref "R30") (pin "1") (pinfunction "1_1") (pintype "passive"))
    )
    (net (code "35") (name "Net-(OK2-A)") (class "Default")
      (node (ref "OK2") (pin "2") (pinfunction "A_2") (pintype "passive"))
      (node (ref "R31") (pin "1") (pinfunction "1_1") (pintype "passive"))
    )
    (net (code "36") (name "Net-(OK3-C)") (class "Default")
      (node (ref "OK3") (pin "2") (pinfunction "C_2") (pintype "passive"))
      (node (ref "R35") (pin "2") (pinfunction "2_2") (pintype "passive"))
    )
    (net (code "37") (name "Net-(OK3-COL)") (class "Default")
      (node (ref "OK3") (pin "4") (pinfunction "COL_4") (pintype "passive"))
      (node (ref "R34") (pin "1") (pinfunction "1_1") (pintype "passive"))
    )
    (net (code "38") (name "Net-(OK4-C)") (class "Default")
      (node (ref "OK4") (pin "2") (pinfunction "C_2") (pintype "passive"))
      (node (ref "R38") (pin "2") (pinfunction "2_2") (pintype "passive"))
    )
    (net (code "39") (name "Net-(OK4-COL)") (class "Default")
      (node (ref "OK4") (pin "4") (pinfunction "COL_4") (pintype "passive"))
      (node (ref "R37") (pin "1") (pinfunction "1_1") (pintype "passive"))
    )
    (net (code "40") (name "Net-(U1-~{RST})") (class "Default")
      (node (ref "JP1") (pin "2") (pinfunction "2_2") (pintype "passive"))
      (node (ref "U1") (pin "4") (pinfunction "~{RST}_4") (pintype "input"))
    )
    (net (code "41") (name "P1_~{RST}") (class "Default")
      (node (ref "IC1") (pin "4") (pinfunction "RESET_4") (pintype "input"))
      (node (ref "JP1") (pin "1") (pinfunction "1_1") (pintype "passive"))
      (node (ref "R8") (pin "1") (pinfunction "1_1") (pintype "passive"))
    )
    (net (code "42") (name "P2_~{RST}") (class "Default")
      (node (ref "IC4") (pin "29") (pinfunction "PC6(/RESET)_29") (pintype "bidirectional"))
      (node (ref "JP1") (pin "3") (pinfunction "3_3") (pintype "passive"))
      (node (ref "R26") (pin "1") (pinfunction "1_1") (pintype "passive"))
    )
    (net (code "43") (name "P_MISO") (class "Default")
      (node (ref "IC1") (pin "2") (pinfunction "(PCINT14/MISO)PB6_2") (pintype "bidirectional"))
      (node (ref "IC4") (pin "16") (pinfunction "PB4(MISO)_16") (pintype "bidirectional"))
      (node (ref "U1") (pin "2") (pinfunction "MISO_2") (pintype "input"))
    )
    (net (code "44") (name "P_MOSI") (class "Default")
      (node (ref "IC1") (pin "1") (pinfunction "(PCINT13/MOSI)PB5_1") (pintype "bidirectional"))
      (node (ref "IC4") (pin "15") (pinfunction "PB3(MOSI/OC2)_15") (pintype "bidirectional"))
      (node (ref "U1") (pin "1") (pinfunction "MOSI_1") (pintype "output"))
    )
    (net (code "45") (name "P_SCK") (class "Default")
      (node (ref "IC1") (pin "3") (pinfunction "(PCINT15/SCK)PB7_3") (pintype "bidirectional"))
      (node (ref "IC4") (pin "17") (pinfunction "PB5(SCK)_17") (pintype "bidirectional"))
      (node (ref "U1") (pin "3") (pinfunction "SCK_3") (pintype "input"))
    )
    (net (code "46") (name "RS_W~{R}") (class "Default")
      (node (ref "IC1") (pin "13") (pinfunction "(PCINT28/XCK1/OC1B)PD4_13") (pintype "bidirectional"))
      (node (ref "IC2") (pin "2") (pinfunction "RE/_2") (pintype "input"))
      (node (ref "IC2") (pin "3") (pinfunction "DE_3") (pintype "input"))
    )
    (net (code "47") (name "RXD2") (class "Default")
      (node (ref "IC1") (pin "10") (pinfunction "(PCINT25/TXD0)PD1_10") (pintype "bidirectional"))
      (node (ref "OK2") (pin "3") (pinfunction "C_3") (pintype "passive"))
    )
    (net (code "48") (name "SENSE_+12") (class "Default")
      (node (ref "C21") (pin "1") (pinfunction "1_1") (pintype "passive"))
      (node (ref "IC1") (pin "34") (pinfunction "(PCINT3/ADC3)PA3_34") (pintype "bidirectional"))
      (node (ref "R18") (pin "1") (pinfunction "1_1") (pintype "passive"))
      (node (ref "R20") (pin "2") (pinfunction "2_2") (pintype "passive"))
    )
    (net (code "49") (name "SENSE_-12") (class "Default")
      (node (ref "C22") (pin "1") (pinfunction "1_1") (pintype "passive"))
      (node (ref "IC1") (pin "35") (pinfunction "(PCINT2/ADC2)PA2_35") (pintype "bidirectional"))
      (node (ref "R19") (pin "1") (pinfunction "1_1") (pintype "passive"))
      (node (ref "R21") (pin "2") (pinfunction "2_2") (pintype "passive"))
    )
    (net (code "50") (name "SENSE_5") (class "Default")
      (node (ref "C23") (pin "1") (pinfunction "1_1") (pintype "passive"))
      (node (ref "IC1") (pin "36") (pinfunction "(PCINT1/ADC1)PA1_36") (pintype "bidirectional"))
      (node (ref "R22") (pin "1") (pinfunction "1_1") (pintype "passive"))
      (node (ref "R24") (pin "2") (pinfunction "2_2") (pintype "passive"))
    )
    (net (code "51") (name "SENSE_24") (class "Default")
      (node (ref "C24") (pin "1") (pinfunction "1_1") (pintype "passive"))
      (node (ref "IC1") (pin "37") (pinfunction "(PCINT0/ADC0)PA0_37") (pintype "bidirectional"))
      (node (ref "R23") (pin "1") (pinfunction "1_1") (pintype "passive"))
      (node (ref "R25") (pin "2") (pinfunction "2_2") (pintype "passive"))
    )
    (net (code "52") (name "SENSE_A") (class "Default")
      (node (ref "C20") (pin "1") (pinfunction "1_1") (pintype "passive"))
      (node (ref "IC1") (pin "31") (pinfunction "(PCINT6/ADC6)PA6_31") (pintype "bidirectional"))
      (node (ref "R12") (pin "1") (pinfunction "1_1") (pintype "passive"))
      (node (ref "R17") (pin "2") (pinfunction "2_2") (pintype "passive"))
    )
    (net (code "53") (name "SENSE_B") (class "Default")
      (node (ref "C19") (pin "1") (pinfunction "1_1") (pintype "passive"))
      (node (ref "IC1") (pin "30") (pinfunction "(PCINT7/ADC7)PA7_30") (pintype "bidirectional"))
      (node (ref "R11") (pin "1") (pinfunction "1_1") (pintype "passive"))
      (node (ref "R16") (pin "2") (pinfunction "2_2") (pintype "passive"))
    )
    (net (code "54") (name "SENSE_EXT_A") (class "Default")
      (node (ref "C18") (pin "1") (pinfunction "1_1") (pintype "passive"))
      (node (ref "IC1") (pin "32") (pinfunction "(PCINT5/ADC5)PA5_32") (pintype "bidirectional"))
      (node (ref "R10") (pin "1") (pinfunction "1_1") (pintype "passive"))
      (node (ref "R15") (pin "2") (pinfunction "2_2") (pintype "passive"))
    )
    (net (code "55") (name "SENSE_EXT_B") (class "Default")
      (node (ref "C17") (pin "1") (pinfunction "1_1") (pintype "passive"))
      (node (ref "IC1") (pin "33") (pinfunction "(PCINT4/ADC4)PA4_33") (pintype "bidirectional"))
      (node (ref "R14") (pin "2") (pinfunction "2_2") (pintype "passive"))
      (node (ref "R9") (pin "1") (pinfunction "1_1") (pintype "passive"))
    )
    (net (code "56") (name "SYS_SYNC") (class "Default")
      (node (ref "J1") (pin "C6") (pinfunction "MS_C6") (pintype "passive"))
    )
    (net (code "57") (name "SYS_USR_04") (class "Default")
      (node (ref "J1") (pin "A12") (pinfunction "MS_A12") (pintype "passive"))
    )
    (net (code "58") (name "SYS_USR_05") (class "Default")
      (node (ref "J1") (pin "C12") (pinfunction "MS_C12") (pintype "passive"))
    )
    (net (code "59") (name "SYS_USR_06") (class "Default")
      (node (ref "J1") (pin "A14") (pinfunction "MS_A14") (pintype "passive"))
    )
    (net (code "60") (name "SYS_USR_07") (class "Default")
      (node (ref "J1") (pin "C14") (pinfunction "MS_C14") (pintype "passive"))
    )
    (net (code "61") (name "SYS_USR_08") (class "Default")
      (node (ref "J1") (pin "A16") (pinfunction "MS_A16") (pintype "passive"))
    )
    (net (code "62") (name "SYS_USR_09") (class "Default")
      (node (ref "J1") (pin "C16") (pinfunction "MS_C16") (pintype "passive"))
    )
    (net (code "63") (name "SYS_USR_10") (class "Default")
      (node (ref "J1") (pin "A18") (pinfunction "MS_A18") (pintype "passive"))
    )
    (net (code "64") (name "SYS_USR_11") (class "Default")
      (node (ref "J1") (pin "C18") (pinfunction "MS_C18") (pintype "passive"))
    )
    (net (code "65") (name "SYS_USR_25") (class "Default")
      (node (ref "J1") (pin "A24") (pinfunction "MS_A24") (pintype "passive"))
    )
    (net (code "66") (name "SYS_USR_26") (class "Default")
      (node (ref "J1") (pin "C24") (pinfunction "MS_C24") (pintype "passive"))
    )
    (net (code "67") (name "SYS_USR_27") (class "Default")
      (node (ref "J1") (pin "A26") (pinfunction "MS_A26") (pintype "passive"))
    )
    (net (code "68") (name "SYS_USR_28") (class "Default")
      (node (ref "J1") (pin "C26") (pinfunction "MS_C26") (pintype "passive"))
    )
    (net (code "69") (name "SYS_USR_29") (class "Default")
      (node (ref "J1") (pin "A28") (pinfunction "MS_A28") (pintype "passive"))
    )
    (net (code "70") (name "SYS_USR_30") (class "Default")
      (node (ref "J1") (pin "C28") (pinfunction "MS_C28") (pintype "passive"))
    )
    (net (code "71") (name "TXD2") (class "Default")
      (node (ref "IC1") (pin "9") (pinfunction "(PCINT24/RXD0)PD0_9") (pintype "bidirectional"))
      (node (ref "OK1") (pin "6") (pinfunction "VO_6") (pintype "passive"))
      (node (ref "R29") (pin "1") (pinfunction "1_1") (pintype "passive"))
    )
    (net (code "72") (name "USBDM") (class "Default")
      (node (ref "IC5") (pin "16") (pinfunction "USBDM_16") (pintype "bidirectional"))
      (node (ref "J1") (pin "C22") (pinfunction "MS_C22") (pintype "passive"))
    )
    (net (code "73") (name "USBDP") (class "Default")
      (node (ref "IC5") (pin "15") (pinfunction "USBDP_15") (pintype "bidirectional"))
      (node (ref "J1") (pin "A22") (pinfunction "MS_A22") (pintype "passive"))
    )
    (net (code "74") (name "V+") (class "Default")
      (node (ref "D1") (pin "A") (pinfunction "A_A") (pintype "passive"))
      (node (ref "J1") (pin "A2") (pinfunction "MS_A2") (pintype "passive"))
      (node (ref "J1") (pin "A8") (pinfunction "MS_A8") (pintype "passive"))
      (node (ref "R23") (pin "2") (pinfunction "2_2") (pintype "passive"))
    )
    (net (code "75") (name "VCCINT") (class "Default")
      (node (ref "C13") (pin "1") (pinfunction "1_1") (pintype "passive"))
      (node (ref "C14") (pin "1") (pinfunction "1_1") (pintype "passive"))
      (node (ref "C16") (pin "1") (pinfunction "1_1") (pintype "passive"))
      (node (ref "IC5") (pin "20") (pinfunction "VCC_20") (pintype "power_in"))
      (node (ref "IC5") (pin "4") (pinfunction "VCCIO_4") (pintype "power_in"))
      (node (ref "J1") (pin "A20") (pinfunction "MS_A20") (pintype "passive"))
      (node (ref "J2") (pin "1") (pinfunction "1_1") (pintype "passive"))
      (node (ref "J2") (pin "2") (pinfunction "2_2") (pintype "passive"))
      (node (ref "OK2") (pin "7") (pinfunction "VE_7") (pintype "passive"))
      (node (ref "OK2") (pin "8") (pinfunction "VCC_8") (pintype "passive"))
      (node (ref "OK3") (pin "1") (pinfunction "A_1") (pintype "passive"))
      (node (ref "OK4") (pin "1") (pinfunction "A_1") (pintype "passive"))
      (node (ref "R30") (pin "2") (pinfunction "2_2") (pintype "passive"))
      (node (ref "R32") (pin "2") (pinfunction "2_2") (pintype "passive"))
    )
    (net (code "76") (name "V_REF") (class "Default")
      (node (ref "C9") (pin "1") (pinfunction "1_1") (pintype "passive"))
      (node (ref "IC1") (pin "29") (pinfunction "AREF_29") (pintype "passive"))
      (node (ref "R13") (pin "1") (pinfunction "1_1") (pintype "passive"))
      (node (ref "VR1") (pin "1") (pinfunction "C_1") (pintype "passive"))
      (node (ref "VR1") (pin "8") (pinfunction "R_8") (pintype "passive"))
    )
    (net (code "77") (name "unconnected-(DC1-COM-Pad5)") (class "Default")
      (node (ref "DC1") (pin "5") (pinfunction "COM_5") (pintype "passive"))
    )
    (net (code "78") (name "unconnected-(IC1-(PCINT12{slash}OC0B{slash}~{SS})PB4-Pad44)") (class "Default")
      (node (ref "IC1") (pin "44") (pinfunction "(PCINT12/OC0B/~{SS})PB4_44") (pintype "bidirectional"))
    )
    (net (code "79") (name "unconnected-(IC1-(PCINT18{slash}TCK)PC2-Pad21)") (class "Default")
      (node (ref "IC1") (pin "21") (pinfunction "(PCINT18/TCK)PC2_21") (pintype "output"))
    )
    (net (code "80") (name "unconnected-(IC1-(PCINT19{slash}TMS)PC3-Pad22)") (class "Default")
      (node (ref "IC1") (pin "22") (pinfunction "(PCINT19/TMS)PC3_22") (pintype "output"))
    )
    (net (code "81") (name "unconnected-(IC1-(PCINT20{slash}TDO)PC4-Pad23)") (class "Default")
      (node (ref "IC1") (pin "23") (pinfunction "(PCINT20/TDO)PC4_23") (pintype "output"))
    )
    (net (code "82") (name "unconnected-(IC1-(PCINT21{slash}TDI)PC5-Pad24)") (class "Default")
      (node (ref "IC1") (pin "24") (pinfunction "(PCINT21/TDI)PC5_24") (pintype "output"))
    )
    (net (code "83") (name "unconnected-(IC1-(PCINT22{slash}TOSC1)PC6-Pad25)") (class "Default")
      (node (ref "IC1") (pin "25") (pinfunction "(PCINT22/TOSC1)PC6_25") (pintype "output"))
    )
    (net (code "84") (name "unconnected-(IC1-(PCINT23{slash}TOSC2)PC7-Pad26)") (class "Default")
      (node (ref "IC1") (pin "26") (pinfunction "(PCINT23/TOSC2)PC7_26") (pintype "output"))
    )
    (net (code "85") (name "unconnected-(IC1-(PCINT29{slash}OC1A)PD5-Pad14)") (class "Default")
      (node (ref "IC1") (pin "14") (pinfunction "(PCINT29/OC1A)PD5_14") (pintype "bidirectional"))
    )
    (net (code "86") (name "unconnected-(IC1-(PCINT30{slash}OC2B{slash}ICP)PD6-Pad15)") (class "Default")
      (node (ref "IC1") (pin "15") (pinfunction "(PCINT30/OC2B/ICP)PD6_15") (pintype "bidirectional"))
    )
    (net (code "87") (name "unconnected-(IC1-(PCINT31{slash}OC2A)PD7-Pad16)") (class "Default")
      (node (ref "IC1") (pin "16") (pinfunction "(PCINT31/OC2A)PD7_16") (pintype "bidirectional"))
    )
    (net (code "88") (name "unconnected-(IC4-ADC6-Pad19)") (class "Default")
      (node (ref "IC4") (pin "19") (pinfunction "ADC6_19") (pintype "bidirectional"))
    )
    (net (code "89") (name "unconnected-(IC4-ADC7-Pad22)") (class "Default")
      (node (ref "IC4") (pin "22") (pinfunction "ADC7_22") (pintype "bidirectional"))
    )
    (net (code "90") (name "unconnected-(IC4-AREF-Pad20)") (class "Default")
      (node (ref "IC4") (pin "20") (pinfunction "AREF_20") (pintype "passive"))
    )
    (net (code "91") (name "unconnected-(IC4-PB0(ICP)-Pad12)") (class "Default")
      (node (ref "IC4") (pin "12") (pinfunction "PB0(ICP)_12") (pintype "bidirectional"))
    )
    (net (code "92") (name "unconnected-(IC4-PB1(OC1A)-Pad13)") (class "Default")
      (node (ref "IC4") (pin "13") (pinfunction "PB1(OC1A)_13") (pintype "bidirectional"))
    )
    (net (code "93") (name "unconnected-(IC4-PB2(SS{slash}OC1B)-Pad14)") (class "Default")
      (node (ref "IC4") (pin "14") (pinfunction "PB2(SS/OC1B)_14") (pintype "bidirectional"))
    )
    (net (code "94") (name "unconnected-(IC4-PB7(XTAL2{slash}TOSC2)-Pad8)") (class "Default")
      (node (ref "IC4") (pin "8") (pinfunction "PB7(XTAL2/TOSC2)_8") (pintype "bidirectional"))
    )
    (net (code "95") (name "unconnected-(IC4-PC3(ADC3)-Pad26)") (class "Default")
      (node (ref "IC4") (pin "26") (pinfunction "PC3(ADC3)_26") (pintype "bidirectional"))
    )
    (net (code "96") (name "unconnected-(IC4-PD3(INT1)-Pad1)") (class "Default")
      (node (ref "IC4") (pin "1") (pinfunction "PD3(INT1)_1") (pintype "bidirectional"))
    )
    (net (code "97") (name "unconnected-(IC4-PD4(XCK{slash}T0)-Pad2)") (class "Default")
      (node (ref "IC4") (pin "2") (pinfunction "PD4(XCK/T0)_2") (pintype "bidirectional"))
    )
    (net (code "98") (name "unconnected-(IC4-PD5(T1)-Pad9)") (class "Default")
      (node (ref "IC4") (pin "9") (pinfunction "PD5(T1)_9") (pintype "bidirectional"))
    )
    (net (code "99") (name "unconnected-(IC4-PD6(AIN0)-Pad10)") (class "Default")
      (node (ref "IC4") (pin "10") (pinfunction "PD6(AIN0)_10") (pintype "bidirectional"))
    )
    (net (code "100") (name "unconnected-(IC4-PD7(AIN1)-Pad11)") (class "Default")
      (node (ref "IC4") (pin "11") (pinfunction "PD7(AIN1)_11") (pintype "bidirectional"))
    )
    (net (code "101") (name "unconnected-(IC5-CBUS2-Pad13)") (class "Default")
      (node (ref "IC5") (pin "13") (pinfunction "CBUS2_13") (pintype "bidirectional"))
    )
    (net (code "102") (name "unconnected-(IC5-CBUS3-Pad14)") (class "Default")
      (node (ref "IC5") (pin "14") (pinfunction "CBUS3_14") (pintype "bidirectional"))
    )
    (net (code "103") (name "unconnected-(IC5-CBUS4-Pad12)") (class "Default")
      (node (ref "IC5") (pin "12") (pinfunction "CBUS4_12") (pintype "bidirectional"))
    )
    (net (code "104") (name "unconnected-(IC5-NC1-Pad8)") (class "Default")
      (node (ref "IC5") (pin "8") (pinfunction "NC1_8") (pintype "passive"))
    )
    (net (code "105") (name "unconnected-(IC5-NC2-Pad24)") (class "Default")
      (node (ref "IC5") (pin "24") (pinfunction "NC2_24") (pintype "passive"))
    )
    (net (code "106") (name "unconnected-(IC5-OSCI-Pad27)") (class "Default")
      (node (ref "IC5") (pin "27") (pinfunction "OSCI_27") (pintype "input"))
    )
    (net (code "107") (name "unconnected-(IC5-OSCO-Pad28)") (class "Default")
      (node (ref "IC5") (pin "28") (pinfunction "OSCO_28") (pintype "output"))
    )
    (net (code "108") (name "unconnected-(IC5-~{CTS}-Pad11)") (class "Default")
      (node (ref "IC5") (pin "11") (pinfunction "~{CTS}_11") (pintype "input"))
    )
    (net (code "109") (name "unconnected-(IC5-~{DCD}-Pad10)") (class "Default")
      (node (ref "IC5") (pin "10") (pinfunction "~{DCD}_10") (pintype "input"))
    )
    (net (code "110") (name "unconnected-(IC5-~{DSR}-Pad9)") (class "Default")
      (node (ref "IC5") (pin "9") (pinfunction "~{DSR}_9") (pintype "input"))
    )
    (net (code "111") (name "unconnected-(IC5-~{DTR}-Pad2)") (class "Default")
      (node (ref "IC5") (pin "2") (pinfunction "~{DTR}_2") (pintype "output"))
    )
    (net (code "112") (name "unconnected-(IC5-~{RESET}-Pad19)") (class "Default")
      (node (ref "IC5") (pin "19") (pinfunction "~{RESET}_19") (pintype "input"))
    )
    (net (code "113") (name "unconnected-(IC5-~{RI}-Pad6)") (class "Default")
      (node (ref "IC5") (pin "6") (pinfunction "~{RI}_6") (pintype "input"))
    )
    (net (code "114") (name "unconnected-(IC5-~{RTS}-Pad3)") (class "Default")
      (node (ref "IC5") (pin "3") (pinfunction "~{RTS}_3") (pintype "output"))
    )
    (net (code "115") (name "unconnected-(OK1-A1-Pad1)") (class "Default")
      (node (ref "OK1") (pin "1") (pinfunction "A1_1") (pintype "passive"))
    )
    (net (code "116") (name "unconnected-(OK1-A2-Pad4)") (class "Default")
      (node (ref "OK1") (pin "4") (pinfunction "A2_4") (pintype "passive"))
    )
    (net (code "117") (name "unconnected-(OK2-A1-Pad1)") (class "Default")
      (node (ref "OK2") (pin "1") (pinfunction "A1_1") (pintype "passive"))
    )
    (net (code "118") (name "unconnected-(OK2-A2-Pad4)") (class "Default")
      (node (ref "OK2") (pin "4") (pinfunction "A2_4") (pintype "passive"))
    )
  )
)
